# PA_Transmitter_3LD.net
KiCad netlist of a schematic drawn in Altium Designer
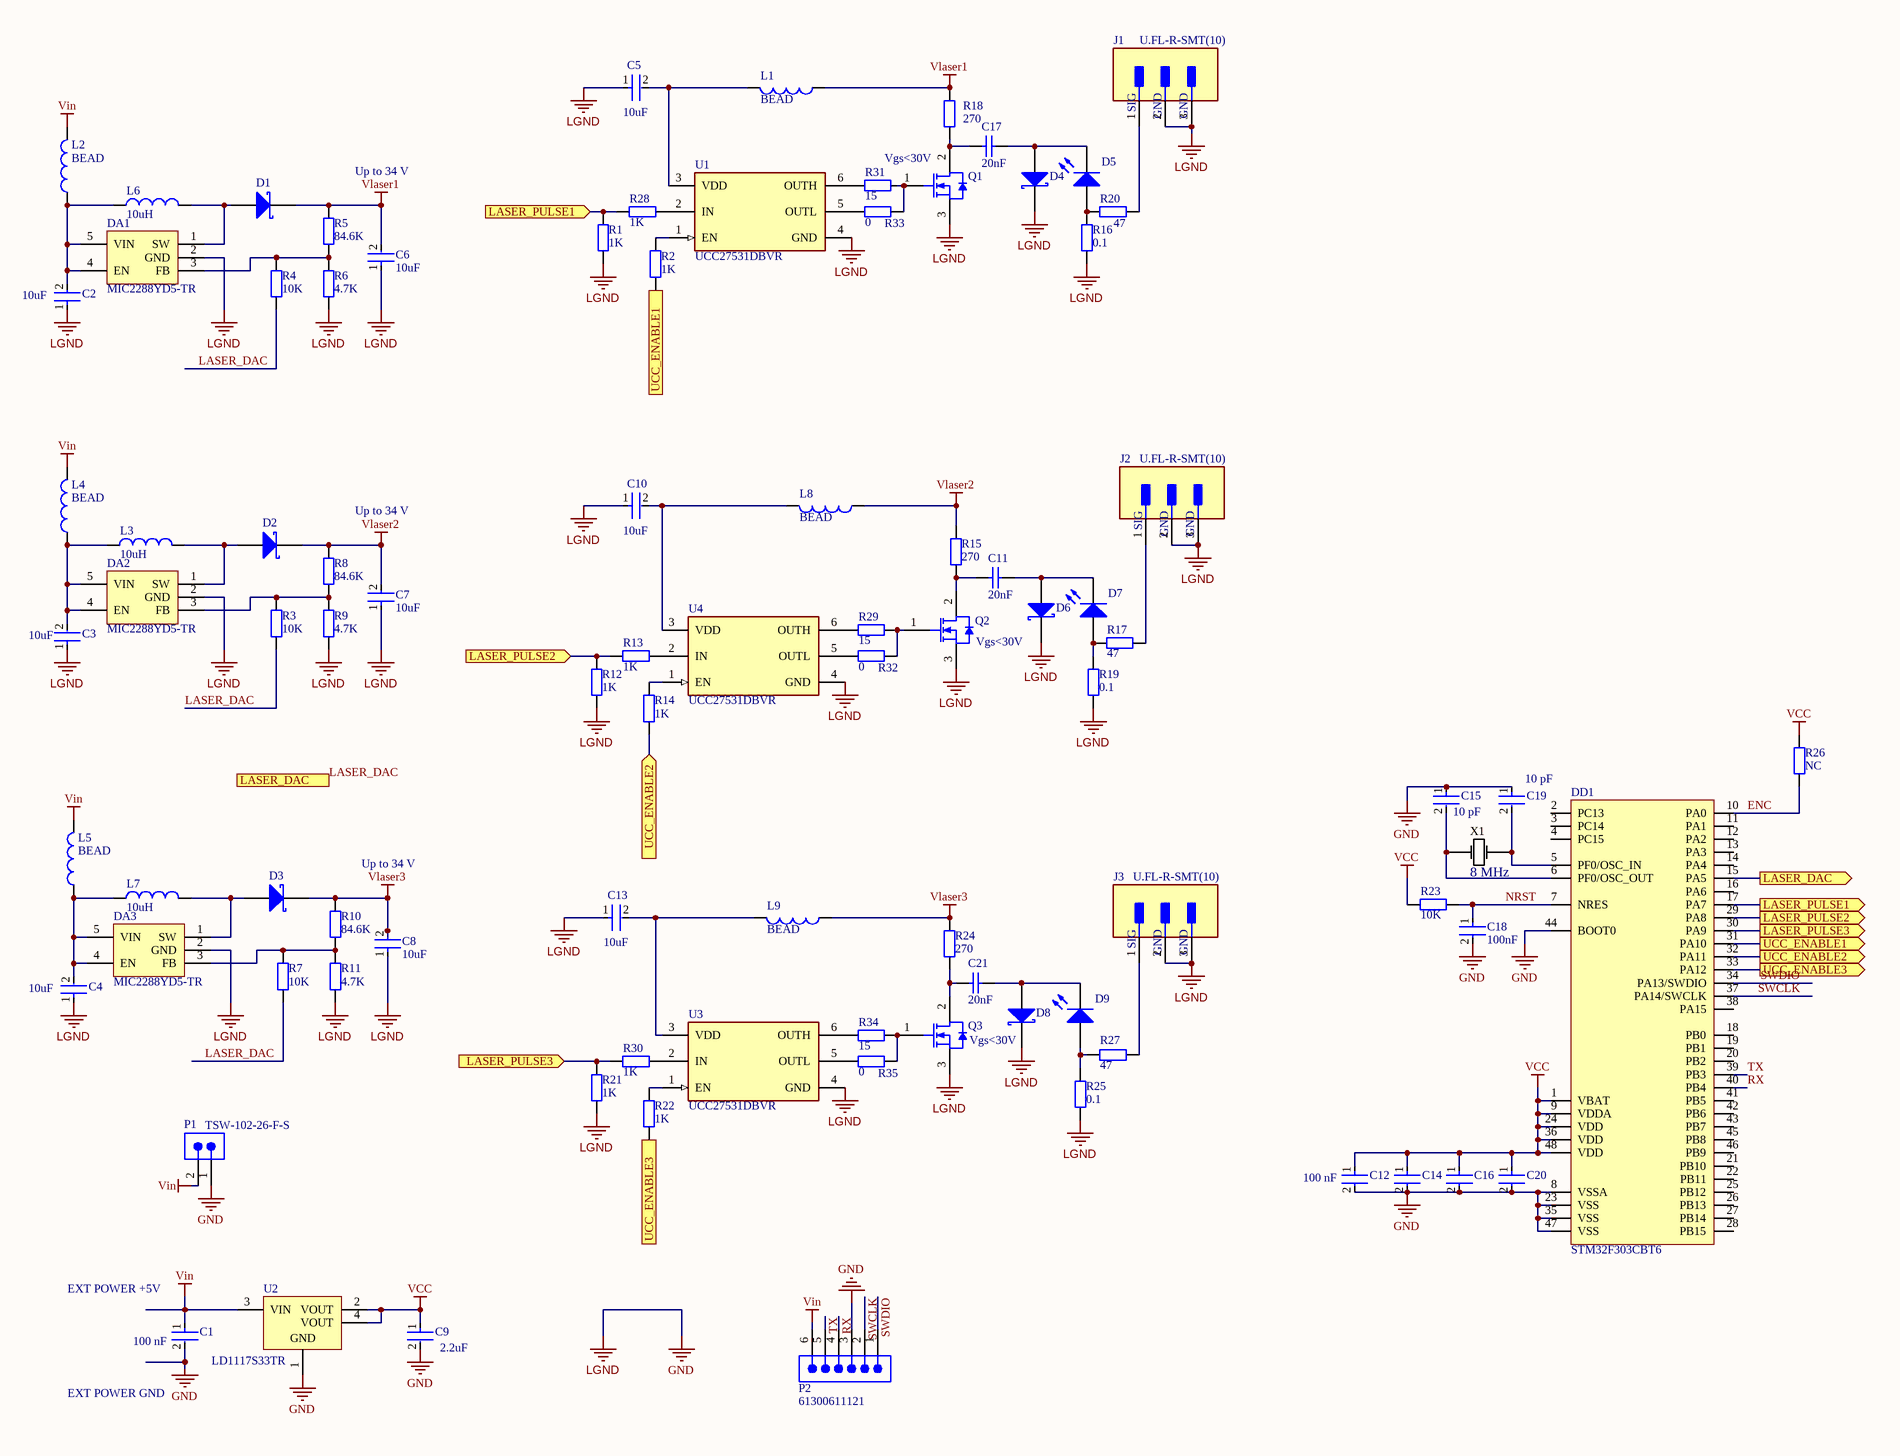
[diagram p0: PA_Transmitter_3LD.SchDoc, right]

(export (version "E")
  (design (tool "Eeschema 10.0.6"))
  (components
    (comp (ref "C1")
      (value "100 nF")
      (footprint "FP-CC0603-DA-MFG")
      (description "CAP CER 0.1UF 16V X7R 0603")
      (fields
        (field (name "OCTOPART") "https://octopart.com/cc0603krx7r7bb104-yageo-192941")
        (field (name "TOLERANCE") "0.1")
      )
      (libsource (lib "Altium Content Vault") (part "11868f565c42a9108669ba33697ecf6"))
    )
    (comp (ref "C2")
      (value "10uF")
      (footprint "FP-CL31B106KBHNNNE-MFG")
      (description "CAP CER 10UF 50V X7R 1206")
      (fields (field (name "MANUFACTURER") "Samsung") (field (name "TOLERANCE") "10%"))
      (libsource (lib "Altium Content Vault") (part "b4654b650e69147ec39a6b967a45e02"))
    )
    (comp (ref "C3")
      (value "10uF")
      (footprint "FP-CL31B106KBHNNNE-MFG")
      (description "CAP CER 10UF 50V X7R 1206")
      (fields (field (name "MANUFACTURER") "Samsung") (field (name "TOLERANCE") "10%"))
      (libsource (lib "Altium Content Vault") (part "b4654b650e69147ec39a6b967a45e02"))
    )
    (comp (ref "C4")
      (value "10uF")
      (footprint "FP-CL31B106KBHNNNE-MFG")
      (description "CAP CER 10UF 50V X7R 1206")
      (fields (field (name "MANUFACTURER") "Samsung") (field (name "TOLERANCE") "10%"))
      (libsource (lib "Altium Content Vault") (part "b4654b650e69147ec39a6b967a45e02"))
    )
    (comp (ref "C5")
      (value "10uF")
      (footprint "FP-CL31B106KBHNNNE-MFG")
      (description "CAP CER 10UF 50V X7R 1206")
      (fields (field (name "MANUFACTURER") "Samsung") (field (name "TOLERANCE") "10%"))
      (libsource (lib "Altium Content Vault") (part "b4654b650e69147ec39a6b967a45e02"))
    )
    (comp (ref "C6")
      (value "10uF")
      (footprint "FP-CL31B106KBHNNNE-MFG")
      (description "CAP CER 10UF 50V X7R 1206")
      (fields (field (name "MANUFACTURER") "Samsung") (field (name "TOLERANCE") "10%"))
      (libsource (lib "Altium Content Vault") (part "b4654b650e69147ec39a6b967a45e02"))
    )
    (comp (ref "C7")
      (value "10uF")
      (footprint "FP-CL31B106KBHNNNE-MFG")
      (description "CAP CER 10UF 50V X7R 1206")
      (fields (field (name "MANUFACTURER") "Samsung") (field (name "TOLERANCE") "10%"))
      (libsource (lib "Altium Content Vault") (part "b4654b650e69147ec39a6b967a45e02"))
    )
    (comp (ref "C8")
      (value "10uF")
      (footprint "FP-CL31B106KBHNNNE-MFG")
      (description "CAP CER 10UF 50V X7R 1206")
      (fields (field (name "MANUFACTURER") "Samsung") (field (name "TOLERANCE") "10%"))
      (libsource (lib "Altium Content Vault") (part "b4654b650e69147ec39a6b967a45e02"))
    )
    (comp (ref "C9")
      (value "~")
      (footprint "FP-CL10-IPC_A")
      (description "Cap Ceramic 2.2uF 10V X7R ±10% Pad SMD 0603 +125°C T/R")
      (fields (field (name "CAPACITANCE") "2.2uF") (field (name "TOLERANCE") "10%"))
      (libsource (lib "Altium Content Vault") (part "b4654b650e69147ec39a6b967a45e02"))
    )
    (comp (ref "C10")
      (value "10uF")
      (footprint "FP-CL31B106KBHNNNE-MFG")
      (description "CAP CER 10UF 50V X7R 1206")
      (fields (field (name "MANUFACTURER") "Samsung") (field (name "TOLERANCE") "10%"))
      (libsource (lib "Altium Content Vault") (part "b4654b650e69147ec39a6b967a45e02"))
    )
    (comp (ref "C11")
      (value "20nF")
      (footprint "RESC2013X60X35NL10T20")
      (description "Chip capacitor")
      (fields (field (name "VOLTAGE") "50V"))
      (libsource (lib "MyLibSch") (part "CC0805"))
    )
    (comp (ref "C12")
      (value "CC0805KRX7R9BB104")
      (footprint "FP-CC0805-0_85-MFG")
      (description "CAP CER 0.1UF 50V X7R 0805")
      (fields
        (field (name "TOLERANCE") "0.1")
        (field (name "CAPACITANCE") "100 nF")
        (field (name "MANUFACTURER") "Yageo")
      )
      (libsource (lib "Altium Content Vault") (part "11868f565c42a9108669ba33697ecf6"))
    )
    (comp (ref "C13")
      (value "10uF")
      (footprint "FP-CL31B106KBHNNNE-MFG")
      (description "CAP CER 10UF 50V X7R 1206")
      (fields (field (name "MANUFACTURER") "Samsung") (field (name "TOLERANCE") "10%"))
      (libsource (lib "Altium Content Vault") (part "b4654b650e69147ec39a6b967a45e02"))
    )
    (comp (ref "C14")
      (value "CC0805KRX7R9BB104")
      (footprint "FP-CC0805-0_85-MFG")
      (description "CAP CER 0.1UF 50V X7R 0805")
      (fields (field (name "TOLERANCE") "0.1") (field (name "MANUFACTURER") "Yageo"))
      (libsource (lib "Altium Content Vault") (part "11868f565c42a9108669ba33697ecf6"))
    )
    (comp (ref "C15")
      (value "10 pF")
      (footprint "FP-C0805C-DN-MFG")
      (description "C0805 10 pF X7R 30ppm/°C 5.00% 50 V")
      (fields
        (field (name "OCTOPART") "https://octopart.com/c0805c100j5ractu-kemet-81794931")
        (field (name "MANUFACTURER PART NUMBER") "C0805C100J5RACTU")
      )
      (libsource (lib "Altium Content Vault") (part "b4654b650e69147ec39a6b967a45e02"))
    )
    (comp (ref "C16")
      (value "CC0805KRX7R9BB104")
      (footprint "FP-CC0805-0_85-MFG")
      (description "CAP CER 0.1UF 50V X7R 0805")
      (fields (field (name "TOLERANCE") "0.1") (field (name "MANUFACTURER") "Yageo"))
      (libsource (lib "Altium Content Vault") (part "11868f565c42a9108669ba33697ecf6"))
    )
    (comp (ref "C17")
      (value "20nF")
      (footprint "RESC2013X60X35ML10T20")
      (description "Chip capacitor")
      (fields (field (name "VOLTAGE") "50V"))
      (libsource (lib "MyLibSch") (part "CC0805"))
    )
    (comp (ref "C18")
      (value "100nF")
      (footprint "FP-CC0805-0_85-MFG")
      (description "CAP CER 0.1UF 50V X7R 0805")
      (fields (field (name "TOLERANCE") "0.1") (field (name "MANUFACTURER PART NUMBER") "CC0805KRX7R9BB104"))
      (libsource (lib "Altium Content Vault") (part "11868f565c42a9108669ba33697ecf6"))
    )
    (comp (ref "C19")
      (value "10 pF")
      (footprint "FP-C0805C-DN-MFG")
      (description "C0805 10 pF X7R 30ppm/°C 5.00% 50 V")
      (fields
        (field (name "OCTOPART") "https://octopart.com/c0805c100j5ractu-kemet-81794931")
        (field (name "MANUFACTURER PART NUMBER") "C0805C100J5RACTU")
      )
      (libsource (lib "Altium Content Vault") (part "b4654b650e69147ec39a6b967a45e02"))
    )
    (comp (ref "C20")
      (value "CC0805KRX7R9BB104")
      (footprint "FP-CC0805-0_85-MFG")
      (description "CAP CER 0.1UF 50V X7R 0805")
      (fields (field (name "TOLERANCE") "0.1") (field (name "MANUFACTURER") "Yageo"))
      (libsource (lib "Altium Content Vault") (part "11868f565c42a9108669ba33697ecf6"))
    )
    (comp (ref "C21")
      (value "20nF")
      (footprint "RESC2013X60X35NL10T20")
      (description "Chip capacitor")
      (fields (field (name "VOLTAGE") "50V"))
      (libsource (lib "MyLibSch") (part "CC0805"))
    )
    (comp (ref "D1")
      (value "Schottky Diode")
      (footprint "FP-PG-SC79-2-MFG")
      (libsource (lib "Simulation Generic Components") (part "Schottky Diode"))
    )
    (comp (ref "D2")
      (value "Schottky Diode")
      (footprint "FP-PG-SC79-2-MFG")
      (libsource (lib "Simulation Generic Components") (part "Schottky Diode"))
    )
    (comp (ref "D3")
      (value "Schottky Diode")
      (footprint "FP-PG-SC79-2-MFG")
      (libsource (lib "Simulation Generic Components") (part "Schottky Diode"))
    )
    (comp (ref "D4")
      (value "Schottky Diode")
      (footprint "FP-PG-SC79-2-MFG")
      (libsource (lib "Simulation Generic Components") (part "Schottky Diode"))
    )
    (comp (ref "D5")
      (value "Light-Emitting Diode")
      (footprint "FP-DPGEW1S09H-MFG")
      (libsource (lib "Simulation Generic Components") (part "LED"))
    )
    (comp (ref "D6")
      (value "Schottky Diode")
      (footprint "FP-PG-SC79-2-MFG")
      (libsource (lib "Simulation Generic Components") (part "Schottky Diode"))
    )
    (comp (ref "D7")
      (value "Light-Emitting Diode")
      (footprint "FP-DPGEW1S09H-MFG")
      (libsource (lib "Simulation Generic Components") (part "LED"))
    )
    (comp (ref "D8")
      (value "Schottky Diode")
      (footprint "FP-PG-SC79-2-MFG")
      (libsource (lib "Simulation Generic Components") (part "Schottky Diode"))
    )
    (comp (ref "D9")
      (value "Light-Emitting Diode")
      (footprint "FP-DPGEW1S09H-MFG")
      (libsource (lib "Simulation Generic Components") (part "LED"))
    )
    (comp (ref "DA1")
      (value "MIC2288YD5-TR")
      (footprint "TSOT-23-5:FP-TSOT-5LD-PL-1-IPC_A")
      (description "Step Up")
      (libsource (lib "lcd_lib") (part "MIC2288"))
    )
    (comp (ref "DA2")
      (value "MIC2288YD5-TR")
      (footprint "FP-TSOT-5LD-PL-1-IPC_A")
      (description "Step Up")
      (libsource (lib "lcd_lib") (part "MIC2288"))
    )
    (comp (ref "DA3")
      (value "MIC2288YD5-TR")
      (footprint "FP-TSOT-5LD-PL-1-IPC_A")
      (description "Step Up")
      (libsource (lib "lcd_lib") (part "MIC2288"))
    )
    (comp (ref "DD1")
      (value "STM32F303CBT6")
      (footprint "STM-LQFP48_L")
      (description "Microcontroller")
      (libsource (lib "lcd_lib") (part "STM32F3_LQFP48"))
    )
    (comp (ref "J1")
      (value "U.FL-R-SMT(10)")
      (footprint "FP-U_FL-R-SMT_10-MFG")
      (description "CONN U.FL RCPT STR 50 OHM SMD")
      (libsource (lib "Altium Content Vault") (part "eef6fde44c591823e8076210edfe12f"))
    )
    (comp (ref "J2")
      (value "U.FL-R-SMT(10)")
      (footprint "FP-U_FL-R-SMT_10-MFG")
      (description "CONN U.FL RCPT STR 50 OHM SMD")
      (libsource (lib "Altium Content Vault") (part "eef6fde44c591823e8076210edfe12f"))
    )
    (comp (ref "J3")
      (value "U.FL-R-SMT(10)")
      (footprint "FP-U_FL-R-SMT_10-MFG")
      (description "CONN U.FL RCPT STR 50 OHM SMD")
      (libsource (lib "Altium Content Vault") (part "eef6fde44c591823e8076210edfe12f"))
    )
    (comp (ref "L1")
      (value "BEAD")
      (footprint "FP-BLM18-0_15-t0_8-IPC_A")
      (description "Ferrit Bead")
      (libsource (lib "MyLibSch") (part "BEAD"))
    )
    (comp (ref "L2")
      (value "BEAD")
      (footprint "FP-BLM18-0_15-t0_8-IPC_A")
      (description "Ferrit Bead")
      (libsource (lib "MyLibSch") (part "BEAD"))
    )
    (comp (ref "L3")
      (value "10uH")
      (footprint "RESC2013X60X35LL10T20")
      (description "Inductor")
      (libsource (lib "Simulation Generic Components") (part "Inductor"))
    )
    (comp (ref "L4")
      (value "BEAD")
      (footprint "FP-BLM18-0_15-t0_8-IPC_A")
      (description "Ferrit Bead")
      (libsource (lib "MyLibSch") (part "BEAD"))
    )
    (comp (ref "L5")
      (value "BEAD")
      (footprint "FP-BLM18-0_15-t0_8-IPC_A")
      (description "Ferrit Bead")
      (libsource (lib "MyLibSch") (part "BEAD"))
    )
    (comp (ref "L6")
      (value "10uH")
      (footprint "RESC2013X60X35LL10T20")
      (description "Inductor")
      (libsource (lib "Simulation Generic Components") (part "Inductor"))
    )
    (comp (ref "L7")
      (value "10uH")
      (footprint "RESC2013X60X35LL10T20")
      (description "Inductor")
      (libsource (lib "Simulation Generic Components") (part "Inductor"))
    )
    (comp (ref "L8")
      (value "BEAD")
      (footprint "FP-BLM18-0_15-t0_8-IPC_A")
      (description "Ferrit Bead")
      (libsource (lib "MyLibSch") (part "BEAD"))
    )
    (comp (ref "L9")
      (value "BEAD")
      (footprint "FP-BLM18-0_15-t0_8-IPC_A")
      (description "Ferrit Bead")
      (libsource (lib "MyLibSch") (part "BEAD"))
    )
    (comp (ref "P1")
      (value "TSW-102-26-F-S")
      (footprint "SMTC-TSW-102-26-XX-S")
      (description "0.025\" SQ Post Header, Through-hole, Vertical, -55 to 125 degC, 2.54 mm Pitch, 2-Pin, Male, RoHS")
      (fields (field (name "MANUFACTURER") "Samtec"))
      (libsource (lib "Altium Content Vault") (part "SMTC-TSW-102-X-X-S-X"))
    )
    (comp (ref "P2")
      (value "61300611121")
      (footprint "61300611121")
      (libsource (lib "Altium Content Vault") (part "Header_Male_1R_06P"))
    )
    (comp (ref "Q1")
      (value "~")
      (footprint "INF-PG-TO252-3-313_N")
      (fields (field (name "MANUFACTURER") "Infineon") (field (name "PARTNUMBER") "IPD60R520C6"))
      (libsource (lib "Components - 15.04.25 - 21.51") (part "CMP-1164-00353-1"))
    )
    (comp (ref "Q2")
      (value "~")
      (footprint "INF-PG-TO252-3-313_N")
      (fields (field (name "MANUFACTURER") "Infineon") (field (name "PARTNUMBER") "IPD60R520C6"))
      (libsource (lib "Components - 15.04.25 - 21.51") (part "CMP-1164-00353-1"))
    )
    (comp (ref "Q3")
      (value "~")
      (footprint "INF-PG-TO252-3-313_N")
      (fields (field (name "MANUFACTURER") "Infineon") (field (name "PARTNUMBER") "IPD60R520C6"))
      (libsource (lib "Components - 15.04.25 - 21.51") (part "CMP-1164-00353-1"))
    )
    (comp (ref "R1")
      (value "1K")
      (footprint "RESC2013X60X35ML10T20")
      (description "Chip resistor")
      (fields (field (name "TOLERANCE") "5%"))
      (libsource (lib "") (part "RC0805_1"))
    )
    (comp (ref "R2")
      (value "1K")
      (footprint "RESC2013X60X35ML10T20")
      (description "Chip resistor")
      (fields (field (name "TOLERANCE") "5%"))
      (libsource (lib "") (part "RC0805_1"))
    )
    (comp (ref "R3")
      (value "10K")
      (footprint "RESC2013X60X35ML10T20")
      (description "Chip resistor")
      (fields (field (name "TOLERANCE") "5%"))
      (libsource (lib "") (part "RC0805_1"))
    )
    (comp (ref "R4")
      (value "10K")
      (footprint "RESC2013X60X35ML10T20")
      (description "Chip resistor")
      (fields (field (name "TOLERANCE") "5%"))
      (libsource (lib "") (part "RC0805_1"))
    )
    (comp (ref "R5")
      (value "84.6K")
      (footprint "RESC2013X60X35ML10T20")
      (description "Chip resistor")
      (fields (field (name "TOLERANCE") "5%"))
      (libsource (lib "") (part "RC0805_1"))
    )
    (comp (ref "R6")
      (value "4.7K")
      (footprint "RESC2013X60X35ML10T20")
      (description "Chip resistor")
      (fields (field (name "TOLERANCE") "5%"))
      (libsource (lib "") (part "RC0805_1"))
    )
    (comp (ref "R7")
      (value "10K")
      (footprint "RESC2013X60X35ML10T20")
      (description "Chip resistor")
      (fields (field (name "TOLERANCE") "5%"))
      (libsource (lib "") (part "RC0805_1"))
    )
    (comp (ref "R8")
      (value "84.6K")
      (footprint "RESC2013X60X35ML10T20")
      (description "Chip resistor")
      (fields (field (name "TOLERANCE") "5%"))
      (libsource (lib "") (part "RC0805_1"))
    )
    (comp (ref "R9")
      (value "4.7K")
      (footprint "RESC2013X60X35ML10T20")
      (description "Chip resistor")
      (fields (field (name "TOLERANCE") "5%"))
      (libsource (lib "") (part "RC0805_1"))
    )
    (comp (ref "R10")
      (value "84.6K")
      (footprint "RESC2013X60X35ML10T20")
      (description "Chip resistor")
      (fields (field (name "TOLERANCE") "5%"))
      (libsource (lib "") (part "RC0805_1"))
    )
    (comp (ref "R11")
      (value "4.7K")
      (footprint "RESC2013X60X35ML10T20")
      (description "Chip resistor")
      (fields (field (name "TOLERANCE") "5%"))
      (libsource (lib "") (part "RC0805_1"))
    )
    (comp (ref "R12")
      (value "1K")
      (footprint "RESC2013X60X35ML10T20")
      (description "Chip resistor")
      (fields (field (name "TOLERANCE") "5%"))
      (libsource (lib "") (part "RC0805_1"))
    )
    (comp (ref "R13")
      (value "1K")
      (footprint "RESC2013X60X35ML10T20")
      (description "Chip resistor")
      (fields (field (name "TOLERANCE") "5%"))
      (libsource (lib "") (part "RC0805_2"))
    )
    (comp (ref "R14")
      (value "1K")
      (footprint "RESC2013X60X35ML10T20")
      (description "Chip resistor")
      (fields (field (name "TOLERANCE") "5%"))
      (libsource (lib "") (part "RC0805_1"))
    )
    (comp (ref "R15")
      (value "270")
      (footprint "FP-CL31B106KBHNNNE-IPC_A")
      (description "Chip resistor")
      (fields (field (name "TOLERANCE") "5%"))
      (libsource (lib "") (part "RC0805_1"))
    )
    (comp (ref "R16")
      (value "0.1")
      (footprint "FP-LLL215-0_1-IPC_B")
      (description "Chip resistor")
      (fields (field (name "TOLERANCE") "5%"))
      (libsource (lib "") (part "RC0805_1"))
    )
    (comp (ref "R17")
      (value "47")
      (footprint "RESC2013X60X35ML10T20")
      (description "Chip resistor")
      (fields (field (name "TOLERANCE") "5%"))
      (libsource (lib "") (part "RC0805_2"))
    )
    (comp (ref "R18")
      (value "270")
      (footprint "FP-CL31B106KBHNNNE-IPC_A")
      (description "Chip resistor")
      (fields (field (name "TOLERANCE") "5%"))
      (libsource (lib "") (part "RC0805_1"))
    )
    (comp (ref "R19")
      (value "0.1")
      (footprint "FP-LLL215-0_1-IPC_B")
      (description "Chip resistor")
      (fields (field (name "TOLERANCE") "5%"))
      (libsource (lib "") (part "RC0805_1"))
    )
    (comp (ref "R20")
      (value "47")
      (footprint "RESC2013X60X35ML10T20")
      (description "Chip resistor")
      (fields (field (name "TOLERANCE") "5%"))
      (libsource (lib "MyLibSch") (part "RC0805"))
    )
    (comp (ref "R21")
      (value "1K")
      (footprint "RESC2013X60X35ML10T20")
      (description "Chip resistor")
      (fields (field (name "TOLERANCE") "5%"))
      (libsource (lib "") (part "RC0805_1"))
    )
    (comp (ref "R22")
      (value "1K")
      (footprint "RESC2013X60X35ML10T20")
      (description "Chip resistor")
      (fields (field (name "TOLERANCE") "5%"))
      (libsource (lib "") (part "RC0805_1"))
    )
    (comp (ref "R23")
      (value "10K")
      (footprint "RESC2013X60X35ML10T20")
      (description "Chip resistor")
      (fields (field (name "TOLERANCE") "5%"))
      (libsource (lib "MyLibSch") (part "RC0805"))
    )
    (comp (ref "R24")
      (value "270")
      (footprint "FP-CL31B106KBHNNNE-IPC_A")
      (description "Chip resistor")
      (fields (field (name "TOLERANCE") "5%"))
      (libsource (lib "") (part "RC0805_1"))
    )
    (comp (ref "R25")
      (value "0.1")
      (footprint "FP-LLL215-0_1-IPC_B")
      (description "Chip resistor")
      (fields (field (name "TOLERANCE") "5%"))
      (libsource (lib "") (part "RC0805_1"))
    )
    (comp (ref "R26")
      (value "NC")
      (footprint "RESC2013X60X35ML10T20")
      (description "Chip resistor")
      (fields (field (name "TOLERANCE") "5%"))
      (libsource (lib "") (part "RC0805_3"))
    )
    (comp (ref "R27")
      (value "47")
      (footprint "RESC2013X60X35ML10T20")
      (description "Chip resistor")
      (fields (field (name "TOLERANCE") "5%"))
      (libsource (lib "MyLibSch") (part "RC0805"))
    )
    (comp (ref "R28")
      (value "1K")
      (footprint "RESC2013X60X35ML10T20")
      (description "Chip resistor")
      (fields (field (name "TOLERANCE") "5%"))
      (libsource (lib "") (part "RC0805_2"))
    )
    (comp (ref "R29")
      (value "15")
      (footprint "RESC2013X60X35ML10T20")
      (description "Chip resistor")
      (fields (field (name "TOLERANCE") "5%"))
      (libsource (lib "") (part "RC0805_2"))
    )
    (comp (ref "R30")
      (value "1K")
      (footprint "RESC2013X60X35ML10T20")
      (description "Chip resistor")
      (fields (field (name "TOLERANCE") "5%"))
      (libsource (lib "") (part "RC0805_2"))
    )
    (comp (ref "R31")
      (value "15")
      (footprint "RESC2013X60X35ML10T20")
      (description "Chip resistor")
      (fields (field (name "TOLERANCE") "5%"))
      (libsource (lib "") (part "RC0805_2"))
    )
    (comp (ref "R32")
      (value "0")
      (footprint "RESC2013X60X35ML10T20")
      (description "Chip resistor")
      (fields (field (name "TOLERANCE") "5%"))
      (libsource (lib "") (part "RC0805_2"))
    )
    (comp (ref "R33")
      (value "0")
      (footprint "RESC2013X60X35ML10T20")
      (description "Chip resistor")
      (fields (field (name "TOLERANCE") "5%"))
      (libsource (lib "") (part "RC0805_2"))
    )
    (comp (ref "R34")
      (value "15")
      (footprint "RESC2013X60X35ML10T20")
      (description "Chip resistor")
      (fields (field (name "TOLERANCE") "5%"))
      (libsource (lib "") (part "RC0805_2"))
    )
    (comp (ref "R35")
      (value "0")
      (footprint "RESC2013X60X35ML10T20")
      (description "Chip resistor")
      (fields (field (name "TOLERANCE") "5%"))
      (libsource (lib "") (part "RC0805_2"))
    )
    (comp (ref "U1")
      (value "UCC27531DBVR")
      (footprint "FP-DBV0006A-IPC_B")
      (description "IC GATE DRVR LOW-SIDE SOT23-6")
      (libsource (lib "Altium Content Vault") (part "16a91a241c20d76ff8c7580b319091c"))
    )
    (comp (ref "U2")
      (value "LD1117S33TR")
      (footprint "SOT-223_L")
      (description "Fixed Low Drop Positive Voltage Regulator, 3.3V, 4-Pin SOT-223, Tape and Reel")
      (libsource (lib "Altium Content Vault") (part "PM-REG-LD1117-SOT4"))
    )
    (comp (ref "U3")
      (value "UCC27531DBVR")
      (footprint "FP-DBV0006A-IPC_B")
      (description "IC GATE DRVR LOW-SIDE SOT23-6")
      (libsource (lib "Altium Content Vault") (part "16a91a241c20d76ff8c7580b319091c"))
    )
    (comp (ref "U4")
      (value "UCC27531DBVR")
      (footprint "FP-DBV0006A-IPC_B")
      (description "IC GATE DRVR LOW-SIDE SOT23-6")
      (libsource (lib "Altium Content Vault") (part "16a91a241c20d76ff8c7580b319091c"))
    )
    (comp (ref "X1")
      (value "8 MHz")
      (footprint "FP-ASFL1-MFG")
      (description "Quartz_SX-6 (SMD06035C4)")
      (fields (field (name "Comment") "Quartz"))
      (libsource (lib "lcd_lib") (part "Quartz_SX-6"))
    )
  )
  (nets
    (net (code "1") (name "/ENC") (class "Default")
      (node (ref "DD1") (pin "10") (pinfunction "PA0_10") (pintype "passive"))
      (node (ref "R26") (pin "2") (pinfunction "2_2") (pintype "passive"))
    )
    (net (code "2") (name "/LASER_DAC") (class "Default")
      (node (ref "DD1") (pin "15") (pinfunction "PA5_15") (pintype "passive"))
      (node (ref "R3") (pin "1") (pinfunction "1_1") (pintype "passive"))
      (node (ref "R4") (pin "1") (pinfunction "1_1") (pintype "passive"))
      (node (ref "R7") (pin "1") (pinfunction "1_1") (pintype "passive"))
    )
    (net (code "3") (name "/LASER_PULSE1") (class "Default")
      (node (ref "DD1") (pin "17") (pinfunction "PA7_17") (pintype "passive"))
      (node (ref "R1") (pin "2") (pinfunction "2_2") (pintype "passive"))
      (node (ref "R28") (pin "2") (pinfunction "2_2") (pintype "passive"))
    )
    (net (code "4") (name "/LASER_PULSE2") (class "Default")
      (node (ref "DD1") (pin "29") (pinfunction "PA8_29") (pintype "passive"))
      (node (ref "R12") (pin "2") (pinfunction "2_2") (pintype "passive"))
      (node (ref "R13") (pin "2") (pinfunction "2_2") (pintype "passive"))
    )
    (net (code "5") (name "/LASER_PULSE3") (class "Default")
      (node (ref "DD1") (pin "30") (pinfunction "PA9_30") (pintype "passive"))
      (node (ref "R21") (pin "2") (pinfunction "2_2") (pintype "passive"))
      (node (ref "R30") (pin "2") (pinfunction "2_2") (pintype "passive"))
    )
    (net (code "6") (name "/NRST") (class "Default")
      (node (ref "C18") (pin "1") (pinfunction "1_1") (pintype "passive"))
      (node (ref "DD1") (pin "7") (pinfunction "NRES_7") (pintype "passive"))
      (node (ref "R23") (pin "2") (pinfunction "2_2") (pintype "passive"))
    )
    (net (code "7") (name "/RX") (class "Default")
      (node (ref "DD1") (pin "40") (pinfunction "PB4_40") (pintype "passive"))
      (node (ref "P2") (pin "4") (pinfunction "4_4") (pintype "passive"))
    )
    (net (code "8") (name "/SWCLK") (class "Default")
      (node (ref "DD1") (pin "37") (pinfunction "PA14/SWCLK_37") (pintype "passive"))
      (node (ref "P2") (pin "2") (pinfunction "2_2") (pintype "passive"))
    )
    (net (code "9") (name "/SWDIO") (class "Default")
      (node (ref "DD1") (pin "34") (pinfunction "PA13/SWDIO_34") (pintype "passive"))
      (node (ref "P2") (pin "1") (pinfunction "1_1") (pintype "passive"))
    )
    (net (code "10") (name "/TX") (class "Default")
      (node (ref "DD1") (pin "39") (pinfunction "PB3_39") (pintype "passive"))
      (node (ref "P2") (pin "5") (pinfunction "5_5") (pintype "passive"))
    )
    (net (code "11") (name "/UCC_ENABLE1") (class "Default")
      (node (ref "DD1") (pin "31") (pinfunction "PA10_31") (pintype "passive"))
      (node (ref "R2") (pin "1") (pinfunction "1_1") (pintype "passive"))
    )
    (net (code "12") (name "/UCC_ENABLE2") (class "Default")
      (node (ref "DD1") (pin "32") (pinfunction "PA11_32") (pintype "passive"))
      (node (ref "R14") (pin "1") (pinfunction "1_1") (pintype "passive"))
    )
    (net (code "13") (name "/UCC_ENABLE3") (class "Default")
      (node (ref "DD1") (pin "33") (pinfunction "PA12_33") (pintype "passive"))
      (node (ref "R22") (pin "1") (pinfunction "1_1") (pintype "passive"))
    )
    (net (code "14") (name "GND") (class "Default")
      (node (ref "C1") (pin "2") (pinfunction "2_2") (pintype "passive"))
      (node (ref "C10") (pin "1") (pinfunction "1_1") (pintype "passive"))
      (node (ref "C12") (pin "2") (pinfunction "2_2") (pintype "passive"))
      (node (ref "C13") (pin "1") (pinfunction "1_1") (pintype "passive"))
      (node (ref "C14") (pin "2") (pinfunction "2_2") (pintype "passive"))
      (node (ref "C15") (pin "1") (pinfunction "1_1") (pintype "passive"))
      (node (ref "C16") (pin "2") (pinfunction "2_2") (pintype "passive"))
      (node (ref "C18") (pin "2") (pinfunction "2_2") (pintype "passive"))
      (node (ref "C19") (pin "1") (pinfunction "1_1") (pintype "passive"))
      (node (ref "C2") (pin "1") (pinfunction "1_1") (pintype "passive"))
      (node (ref "C20") (pin "2") (pinfunction "2_2") (pintype "passive"))
      (node (ref "C3") (pin "1") (pinfunction "1_1") (pintype "passive"))
      (node (ref "C4") (pin "1") (pinfunction "1_1") (pintype "passive"))
      (node (ref "C5") (pin "1") (pinfunction "1_1") (pintype "passive"))
      (node (ref "C6") (pin "1") (pinfunction "1_1") (pintype "passive"))
      (node (ref "C7") (pin "1") (pinfunction "1_1") (pintype "passive"))
      (node (ref "C8") (pin "1") (pinfunction "1_1") (pintype "passive"))
      (node (ref "C9") (pin "2") (pinfunction "2_2") (pintype "passive"))
      (node (ref "D4") (pin "2") (pinfunction "K_2") (pintype "passive"))
      (node (ref "D6") (pin "2") (pinfunction "K_2") (pintype "passive"))
      (node (ref "D8") (pin "2") (pinfunction "K_2") (pintype "passive"))
      (node (ref "DA1") (pin "2") (pinfunction "GND_2") (pintype "power_in"))
      (node (ref "DA2") (pin "2") (pinfunction "GND_2") (pintype "power_in"))
      (node (ref "DA3") (pin "2") (pinfunction "GND_2") (pintype "power_in"))
      (node (ref "DD1") (pin "23") (pinfunction "VSS_23") (pintype "passive"))
      (node (ref "DD1") (pin "35") (pinfunction "VSS_35") (pintype "passive"))
      (node (ref "DD1") (pin "44") (pinfunction "BOOT0_44") (pintype "passive"))
      (node (ref "DD1") (pin "47") (pinfunction "VSS_47") (pintype "passive"))
      (node (ref "DD1") (pin "8") (pinfunction "VSSA_8") (pintype "passive"))
      (node (ref "J1") (pin "2") (pinfunction "GND_2") (pintype "power_in"))
      (node (ref "J1") (pin "3") (pinfunction "GND_3") (pintype "power_in"))
      (node (ref "J2") (pin "2") (pinfunction "GND_2") (pintype "power_in"))
      (node (ref "J2") (pin "3") (pinfunction "GND_3") (pintype "power_in"))
      (node (ref "J3") (pin "2") (pinfunction "GND_2") (pintype "power_in"))
      (node (ref "J3") (pin "3") (pinfunction "GND_3") (pintype "power_in"))
      (node (ref "P1") (pin "1") (pinfunction "1_1") (pintype "passive"))
      (node (ref "P2") (pin "3") (pinfunction "3_3") (pintype "passive"))
      (node (ref "Q1") (pin "3") (pinfunction "SOURCE_3") (pintype "passive"))
      (node (ref "Q2") (pin "3") (pinfunction "SOURCE_3") (pintype "passive"))
      (node (ref "Q3") (pin "3") (pinfunction "SOURCE_3") (pintype "passive"))
      (node (ref "R1") (pin "1") (pinfunction "1_1") (pintype "passive"))
      (node (ref "R11") (pin "1") (pinfunction "1_1") (pintype "passive"))
      (node (ref "R12") (pin "1") (pinfunction "1_1") (pintype "passive"))
      (node (ref "R16") (pin "1") (pinfunction "1_1") (pintype "passive"))
      (node (ref "R19") (pin "1") (pinfunction "1_1") (pintype "passive"))
      (node (ref "R21") (pin "1") (pinfunction "1_1") (pintype "passive"))
      (node (ref "R25") (pin "1") (pinfunction "1_1") (pintype "passive"))
      (node (ref "R6") (pin "1") (pinfunction "1_1") (pintype "passive"))
      (node (ref "R9") (pin "1") (pinfunction "1_1") (pintype "passive"))
      (node (ref "U1") (pin "4") (pinfunction "GND_4") (pintype "power_in"))
      (node (ref "U2") (pin "1") (pinfunction "GND_1") (pintype "power_in"))
      (node (ref "U3") (pin "4") (pinfunction "GND_4") (pintype "power_in"))
      (node (ref "U4") (pin "4") (pinfunction "GND_4") (pintype "power_in"))
    )
    (net (code "15") (name "Net-(D1-A)") (class "Default")
      (node (ref "D1") (pin "1") (pinfunction "A_1") (pintype "passive"))
      (node (ref "DA1") (pin "1") (pinfunction "SW_1") (pintype "open_collector"))
      (node (ref "L6") (pin "2") (pinfunction "2_2") (pintype "passive"))
    )
    (net (code "16") (name "Net-(D2-A)") (class "Default")
      (node (ref "D2") (pin "1") (pinfunction "A_1") (pintype "passive"))
      (node (ref "DA2") (pin "1") (pinfunction "SW_1") (pintype "open_collector"))
      (node (ref "L3") (pin "2") (pinfunction "2_2") (pintype "passive"))
    )
    (net (code "17") (name "Net-(D3-A)") (class "Default")
      (node (ref "D3") (pin "1") (pinfunction "A_1") (pintype "passive"))
      (node (ref "DA3") (pin "1") (pinfunction "SW_1") (pintype "open_collector"))
      (node (ref "L7") (pin "2") (pinfunction "2_2") (pintype "passive"))
    )
    (net (code "18") (name "Net-(D4-A)") (class "Default")
      (node (ref "C17") (pin "1") (pinfunction "1_1") (pintype "passive"))
      (node (ref "D4") (pin "1") (pinfunction "A_1") (pintype "passive"))
      (node (ref "D5") (pin "2") (pinfunction "K_2") (pintype "passive"))
    )
    (net (code "19") (name "Net-(D5-A)") (class "Default")
      (node (ref "D5") (pin "1") (pinfunction "A_1") (pintype "passive"))
      (node (ref "R16") (pin "2") (pinfunction "2_2") (pintype "passive"))
      (node (ref "R20") (pin "1") (pinfunction "1_1") (pintype "passive"))
    )
    (net (code "20") (name "Net-(D6-A)") (class "Default")
      (node (ref "C11") (pin "1") (pinfunction "1_1") (pintype "passive"))
      (node (ref "D6") (pin "1") (pinfunction "A_1") (pintype "passive"))
      (node (ref "D7") (pin "2") (pinfunction "K_2") (pintype "passive"))
    )
    (net (code "21") (name "Net-(D7-A)") (class "Default")
      (node (ref "D7") (pin "1") (pinfunction "A_1") (pintype "passive"))
      (node (ref "R17") (pin "2") (pinfunction "2_2") (pintype "passive"))
      (node (ref "R19") (pin "2") (pinfunction "2_2") (pintype "passive"))
    )
    (net (code "22") (name "Net-(D8-A)") (class "Default")
      (node (ref "C21") (pin "1") (pinfunction "1_1") (pintype "passive"))
      (node (ref "D8") (pin "1") (pinfunction "A_1") (pintype "passive"))
      (node (ref "D9") (pin "2") (pinfunction "K_2") (pintype "passive"))
    )
    (net (code "23") (name "Net-(D9-A)") (class "Default")
      (node (ref "D9") (pin "1") (pinfunction "A_1") (pintype "passive"))
      (node (ref "R25") (pin "2") (pinfunction "2_2") (pintype "passive"))
      (node (ref "R27") (pin "1") (pinfunction "1_1") (pintype "passive"))
    )
    (net (code "24") (name "Net-(DA1-EN)") (class "Default")
      (node (ref "C2") (pin "2") (pinfunction "2_2") (pintype "passive"))
      (node (ref "DA1") (pin "4") (pinfunction "EN_4") (pintype "power_in"))
      (node (ref "DA1") (pin "5") (pinfunction "VIN_5") (pintype "passive"))
      (node (ref "L2") (pin "1") (pinfunction "1_1") (pintype "passive"))
      (node (ref "L6") (pin "1") (pinfunction "1_1") (pintype "passive"))
    )
    (net (code "25") (name "Net-(DA1-FB)") (class "Default")
      (node (ref "DA1") (pin "3") (pinfunction "FB_3") (pintype "power_in"))
      (node (ref "R4") (pin "2") (pinfunction "2_2") (pintype "passive"))
      (node (ref "R5") (pin "1") (pinfunction "1_1") (pintype "passive"))
      (node (ref "R6") (pin "2") (pinfunction "2_2") (pintype "passive"))
    )
    (net (code "26") (name "Net-(DA2-EN)") (class "Default")
      (node (ref "C3") (pin "2") (pinfunction "2_2") (pintype "passive"))
      (node (ref "DA2") (pin "4") (pinfunction "EN_4") (pintype "power_in"))
      (node (ref "DA2") (pin "5") (pinfunction "VIN_5") (pintype "passive"))
      (node (ref "L3") (pin "1") (pinfunction "1_1") (pintype "passive"))
      (node (ref "L4") (pin "1") (pinfunction "1_1") (pintype "passive"))
    )
    (net (code "27") (name "Net-(DA2-FB)") (class "Default")
      (node (ref "DA2") (pin "3") (pinfunction "FB_3") (pintype "power_in"))
      (node (ref "R3") (pin "2") (pinfunction "2_2") (pintype "passive"))
      (node (ref "R8") (pin "1") (pinfunction "1_1") (pintype "passive"))
      (node (ref "R9") (pin "2") (pinfunction "2_2") (pintype "passive"))
    )
    (net (code "28") (name "Net-(DA3-EN)") (class "Default")
      (node (ref "C4") (pin "2") (pinfunction "2_2") (pintype "passive"))
      (node (ref "DA3") (pin "4") (pinfunction "EN_4") (pintype "power_in"))
      (node (ref "DA3") (pin "5") (pinfunction "VIN_5") (pintype "passive"))
      (node (ref "L5") (pin "1") (pinfunction "1_1") (pintype "passive"))
      (node (ref "L7") (pin "1") (pinfunction "1_1") (pintype "passive"))
    )
    (net (code "29") (name "Net-(DA3-FB)") (class "Default")
      (node (ref "DA3") (pin "3") (pinfunction "FB_3") (pintype "power_in"))
      (node (ref "R10") (pin "1") (pinfunction "1_1") (pintype "passive"))
      (node (ref "R11") (pin "2") (pinfunction "2_2") (pintype "passive"))
      (node (ref "R7") (pin "2") (pinfunction "2_2") (pintype "passive"))
    )
    (net (code "30") (name "Net-(DD1-PF0{slash}OSC_IN)") (class "Default")
      (node (ref "C19") (pin "2") (pinfunction "2_2") (pintype "passive"))
      (node (ref "DD1") (pin "5") (pinfunction "PF0/OSC_IN_5") (pintype "passive"))
      (node (ref "X1") (pin "3") (pinfunction "3_3") (pintype "passive"))
    )
    (net (code "31") (name "Net-(DD1-PF0{slash}OSC_OUT)") (class "Default")
      (node (ref "C15") (pin "2") (pinfunction "2_2") (pintype "passive"))
      (node (ref "DD1") (pin "6") (pinfunction "PF0/OSC_OUT_6") (pintype "passive"))
      (node (ref "X1") (pin "1") (pinfunction "1_1") (pintype "passive"))
    )
    (net (code "32") (name "Net-(J1-SIG)") (class "Default")
      (node (ref "J1") (pin "1") (pinfunction "SIG_1") (pintype "passive"))
      (node (ref "R20") (pin "2") (pinfunction "2_2") (pintype "passive"))
    )
    (net (code "33") (name "Net-(J2-SIG)") (class "Default")
      (node (ref "J2") (pin "1") (pinfunction "SIG_1") (pintype "passive"))
      (node (ref "R17") (pin "1") (pinfunction "1_1") (pintype "passive"))
    )
    (net (code "34") (name "Net-(J3-SIG)") (class "Default")
      (node (ref "J3") (pin "1") (pinfunction "SIG_1") (pintype "passive"))
      (node (ref "R27") (pin "2") (pinfunction "2_2") (pintype "passive"))
    )
    (net (code "35") (name "Net-(Q1-DRAIN)") (class "Default")
      (node (ref "C17") (pin "2") (pinfunction "2_2") (pintype "passive"))
      (node (ref "Q1") (pin "2") (pinfunction "DRAIN_2") (pintype "passive"))
      (node (ref "R18") (pin "1") (pinfunction "1_1") (pintype "passive"))
    )
    (net (code "36") (name "Net-(Q1-GATE)") (class "Default")
      (node (ref "Q1") (pin "1") (pinfunction "GATE_1") (pintype "passive"))
      (node (ref "R31") (pin "1") (pinfunction "1_1") (pintype "passive"))
      (node (ref "R33") (pin "1") (pinfunction "1_1") (pintype "passive"))
    )
    (net (code "37") (name "Net-(Q2-DRAIN)") (class "Default")
      (node (ref "C11") (pin "2") (pinfunction "2_2") (pintype "passive"))
      (node (ref "Q2") (pin "2") (pinfunction "DRAIN_2") (pintype "passive"))
      (node (ref "R15") (pin "1") (pinfunction "1_1") (pintype "passive"))
    )
    (net (code "38") (name "Net-(Q2-GATE)") (class "Default")
      (node (ref "Q2") (pin "1") (pinfunction "GATE_1") (pintype "passive"))
      (node (ref "R29") (pin "1") (pinfunction "1_1") (pintype "passive"))
      (node (ref "R32") (pin "1") (pinfunction "1_1") (pintype "passive"))
    )
    (net (code "39") (name "Net-(Q3-DRAIN)") (class "Default")
      (node (ref "C21") (pin "2") (pinfunction "2_2") (pintype "passive"))
      (node (ref "Q3") (pin "2") (pinfunction "DRAIN_2") (pintype "passive"))
      (node (ref "R24") (pin "1") (pinfunction "1_1") (pintype "passive"))
    )
    (net (code "40") (name "Net-(Q3-GATE)") (class "Default")
      (node (ref "Q3") (pin "1") (pinfunction "GATE_1") (pintype "passive"))
      (node (ref "R34") (pin "1") (pinfunction "1_1") (pintype "passive"))
      (node (ref "R35") (pin "1") (pinfunction "1_1") (pintype "passive"))
    )
    (net (code "41") (name "Net-(U1-EN)") (class "Default")
      (node (ref "R2") (pin "2") (pinfunction "2_2") (pintype "passive"))
      (node (ref "U1") (pin "1") (pinfunction "EN_1") (pintype "input"))
    )
    (net (code "42") (name "Net-(U1-IN)") (class "Default")
      (node (ref "R28") (pin "1") (pinfunction "1_1") (pintype "passive"))
      (node (ref "U1") (pin "2") (pinfunction "IN_2") (pintype "tri_state"))
    )
    (net (code "43") (name "Net-(U1-OUTH)") (class "Default")
      (node (ref "R31") (pin "2") (pinfunction "2_2") (pintype "passive"))
      (node (ref "U1") (pin "6") (pinfunction "OUTH_6") (pintype "passive"))
    )
    (net (code "44") (name "Net-(U1-OUTL)") (class "Default")
      (node (ref "R33") (pin "2") (pinfunction "2_2") (pintype "passive"))
      (node (ref "U1") (pin "5") (pinfunction "OUTL_5") (pintype "passive"))
    )
    (net (code "45") (name "Net-(U1-VDD)") (class "Default")
      (node (ref "C5") (pin "2") (pinfunction "2_2") (pintype "passive"))
      (node (ref "L1") (pin "2") (pinfunction "2_2") (pintype "passive"))
      (node (ref "U1") (pin "3") (pinfunction "VDD_3") (pintype "power_in"))
    )
    (net (code "46") (name "Net-(U3-EN)") (class "Default")
      (node (ref "R22") (pin "2") (pinfunction "2_2") (pintype "passive"))
      (node (ref "U3") (pin "1") (pinfunction "EN_1") (pintype "input"))
    )
    (net (code "47") (name "Net-(U3-IN)") (class "Default")
      (node (ref "R30") (pin "1") (pinfunction "1_1") (pintype "passive"))
      (node (ref "U3") (pin "2") (pinfunction "IN_2") (pintype "tri_state"))
    )
    (net (code "48") (name "Net-(U3-OUTH)") (class "Default")
      (node (ref "R34") (pin "2") (pinfunction "2_2") (pintype "passive"))
      (node (ref "U3") (pin "6") (pinfunction "OUTH_6") (pintype "passive"))
    )
    (net (code "49") (name "Net-(U3-OUTL)") (class "Default")
      (node (ref "R35") (pin "2") (pinfunction "2_2") (pintype "passive"))
      (node (ref "U3") (pin "5") (pinfunction "OUTL_5") (pintype "passive"))
    )
    (net (code "50") (name "Net-(U3-VDD)") (class "Default")
      (node (ref "C13") (pin "2") (pinfunction "2_2") (pintype "passive"))
      (node (ref "L9") (pin "2") (pinfunction "2_2") (pintype "passive"))
      (node (ref "U3") (pin "3") (pinfunction "VDD_3") (pintype "power_in"))
    )
    (net (code "51") (name "Net-(U4-EN)") (class "Default")
      (node (ref "R14") (pin "2") (pinfunction "2_2") (pintype "passive"))
      (node (ref "U4") (pin "1") (pinfunction "EN_1") (pintype "input"))
    )
    (net (code "52") (name "Net-(U4-IN)") (class "Default")
      (node (ref "R13") (pin "1") (pinfunction "1_1") (pintype "passive"))
      (node (ref "U4") (pin "2") (pinfunction "IN_2") (pintype "tri_state"))
    )
    (net (code "53") (name "Net-(U4-OUTH)") (class "Default")
      (node (ref "R29") (pin "2") (pinfunction "2_2") (pintype "passive"))
      (node (ref "U4") (pin "6") (pinfunction "OUTH_6") (pintype "passive"))
    )
    (net (code "54") (name "Net-(U4-OUTL)") (class "Default")
      (node (ref "R32") (pin "2") (pinfunction "2_2") (pintype "passive"))
      (node (ref "U4") (pin "5") (pinfunction "OUTL_5") (pintype "passive"))
    )
    (net (code "55") (name "Net-(U4-VDD)") (class "Default")
      (node (ref "C10") (pin "2") (pinfunction "2_2") (pintype "passive"))
      (node (ref "L8") (pin "2") (pinfunction "2_2") (pintype "passive"))
      (node (ref "U4") (pin "3") (pinfunction "VDD_3") (pintype "power_in"))
    )
    (net (code "56") (name "VCC") (class "Default")
      (node (ref "C12") (pin "1") (pinfunction "1_1") (pintype "passive"))
      (node (ref "C14") (pin "1") (pinfunction "1_1") (pintype "passive"))
      (node (ref "C16") (pin "1") (pinfunction "1_1") (pintype "passive"))
      (node (ref "C20") (pin "1") (pinfunction "1_1") (pintype "passive"))
      (node (ref "C9") (pin "1") (pinfunction "1_1") (pintype "passive"))
      (node (ref "DD1") (pin "1") (pinfunction "VBAT_1") (pintype "passive"))
      (node (ref "DD1") (pin "24") (pinfunction "VDD_24") (pintype "passive"))
      (node (ref "DD1") (pin "36") (pinfunction "VDD_36") (pintype "passive"))
      (node (ref "DD1") (pin "48") (pinfunction "VDD_48") (pintype "passive"))
      (node (ref "DD1") (pin "9") (pinfunction "VDDA_9") (pintype "passive"))
      (node (ref "R23") (pin "1") (pinfunction "1_1") (pintype "passive"))
      (node (ref "R26") (pin "1") (pinfunction "1_1") (pintype "passive"))
      (node (ref "U2") (pin "2") (pinfunction "VOUT_2") (pintype "power_in"))
      (node (ref "U2") (pin "4") (pinfunction "VOUT_4") (pintype "power_in"))
    )
    (net (code "57") (name "Vin") (class "Default")
      (node (ref "C1") (pin "1") (pinfunction "1_1") (pintype "passive"))
      (node (ref "L2") (pin "2") (pinfunction "2_2") (pintype "passive"))
      (node (ref "L4") (pin "2") (pinfunction "2_2") (pintype "passive"))
      (node (ref "L5") (pin "2") (pinfunction "2_2") (pintype "passive"))
      (node (ref "P1") (pin "2") (pinfunction "2_2") (pintype "passive"))
      (node (ref "P2") (pin "6") (pinfunction "6_6") (pintype "passive"))
      (node (ref "U2") (pin "3") (pinfunction "VIN_3") (pintype "power_in"))
    )
    (net (code "58") (name "Vlaser1") (class "Default")
      (node (ref "C6") (pin "2") (pinfunction "2_2") (pintype "passive"))
      (node (ref "D1") (pin "2") (pinfunction "K_2") (pintype "passive"))
      (node (ref "L1") (pin "1") (pinfunction "1_1") (pintype "passive"))
      (node (ref "R18") (pin "2") (pinfunction "2_2") (pintype "passive"))
      (node (ref "R5") (pin "2") (pinfunction "2_2") (pintype "passive"))
    )
    (net (code "59") (name "Vlaser2") (class "Default")
      (node (ref "C7") (pin "2") (pinfunction "2_2") (pintype "passive"))
      (node (ref "D2") (pin "2") (pinfunction "K_2") (pintype "passive"))
      (node (ref "L8") (pin "1") (pinfunction "1_1") (pintype "passive"))
      (node (ref "R15") (pin "2") (pinfunction "2_2") (pintype "passive"))
      (node (ref "R8") (pin "2") (pinfunction "2_2") (pintype "passive"))
    )
    (net (code "60") (name "Vlaser3") (class "Default")
      (node (ref "C8") (pin "2") (pinfunction "2_2") (pintype "passive"))
      (node (ref "D3") (pin "2") (pinfunction "K_2") (pintype "passive"))
      (node (ref "L9") (pin "1") (pinfunction "1_1") (pintype "passive"))
      (node (ref "R10") (pin "2") (pinfunction "2_2") (pintype "passive"))
      (node (ref "R24") (pin "2") (pinfunction "2_2") (pintype "passive"))
    )
    (net (code "61") (name "unconnected-(DD1-PA1-Pad11)") (class "Default")
      (node (ref "DD1") (pin "11") (pinfunction "PA1_11") (pintype "passive"))
    )
    (net (code "62") (name "unconnected-(DD1-PA2-Pad12)") (class "Default")
      (node (ref "DD1") (pin "12") (pinfunction "PA2_12") (pintype "passive"))
    )
    (net (code "63") (name "unconnected-(DD1-PA3-Pad13)") (class "Default")
      (node (ref "DD1") (pin "13") (pinfunction "PA3_13") (pintype "passive"))
    )
    (net (code "64") (name "unconnected-(DD1-PA4-Pad14)") (class "Default")
      (node (ref "DD1") (pin "14") (pinfunction "PA4_14") (pintype "passive"))
    )
    (net (code "65") (name "unconnected-(DD1-PA6-Pad16)") (class "Default")
      (node (ref "DD1") (pin "16") (pinfunction "PA6_16") (pintype "passive"))
    )
    (net (code "66") (name "unconnected-(DD1-PA15-Pad38)") (class "Default")
      (node (ref "DD1") (pin "38") (pinfunction "PA15_38") (pintype "passive"))
    )
    (net (code "67") (name "unconnected-(DD1-PB0-Pad18)") (class "Default")
      (node (ref "DD1") (pin "18") (pinfunction "PB0_18") (pintype "passive"))
    )
    (net (code "68") (name "unconnected-(DD1-PB1-Pad19)") (class "Default")
      (node (ref "DD1") (pin "19") (pinfunction "PB1_19") (pintype "passive"))
    )
    (net (code "69") (name "unconnected-(DD1-PB2-Pad20)") (class "Default")
      (node (ref "DD1") (pin "20") (pinfunction "PB2_20") (pintype "passive"))
    )
    (net (code "70") (name "unconnected-(DD1-PB5-Pad41)") (class "Default")
      (node (ref "DD1") (pin "41") (pinfunction "PB5_41") (pintype "passive"))
    )
    (net (code "71") (name "unconnected-(DD1-PB6-Pad42)") (class "Default")
      (node (ref "DD1") (pin "42") (pinfunction "PB6_42") (pintype "passive"))
    )
    (net (code "72") (name "unconnected-(DD1-PB7-Pad43)") (class "Default")
      (node (ref "DD1") (pin "43") (pinfunction "PB7_43") (pintype "passive"))
    )
    (net (code "73") (name "unconnected-(DD1-PB8-Pad45)") (class "Default")
      (node (ref "DD1") (pin "45") (pinfunction "PB8_45") (pintype "passive"))
    )
    (net (code "74") (name "unconnected-(DD1-PB9-Pad46)") (class "Default")
      (node (ref "DD1") (pin "46") (pinfunction "PB9_46") (pintype "passive"))
    )
    (net (code "75") (name "unconnected-(DD1-PB10-Pad21)") (class "Default")
      (node (ref "DD1") (pin "21") (pinfunction "PB10_21") (pintype "passive"))
    )
    (net (code "76") (name "unconnected-(DD1-PB11-Pad22)") (class "Default")
      (node (ref "DD1") (pin "22") (pinfunction "PB11_22") (pintype "passive"))
    )
    (net (code "77") (name "unconnected-(DD1-PB12-Pad25)") (class "Default")
      (node (ref "DD1") (pin "25") (pinfunction "PB12_25") (pintype "passive"))
    )
    (net (code "78") (name "unconnected-(DD1-PB13-Pad26)") (class "Default")
      (node (ref "DD1") (pin "26") (pinfunction "PB13_26") (pintype "passive"))
    )
    (net (code "79") (name "unconnected-(DD1-PB14-Pad27)") (class "Default")
      (node (ref "DD1") (pin "27") (pinfunction "PB14_27") (pintype "passive"))
    )
    (net (code "80") (name "unconnected-(DD1-PB15-Pad28)") (class "Default")
      (node (ref "DD1") (pin "28") (pinfunction "PB15_28") (pintype "passive"))
    )
    (net (code "81") (name "unconnected-(DD1-PC13-Pad2)") (class "Default")
      (node (ref "DD1") (pin "2") (pinfunction "PC13_2") (pintype "passive"))
    )
    (net (code "82") (name "unconnected-(DD1-PC14-Pad3)") (class "Default")
      (node (ref "DD1") (pin "3") (pinfunction "PC14_3") (pintype "passive"))
    )
    (net (code "83") (name "unconnected-(DD1-PC15-Pad4)") (class "Default")
      (node (ref "DD1") (pin "4") (pinfunction "PC15_4") (pintype "passive"))
    )
  )
)
